# ADC-DMUX.net
KiCad netlist of a schematic drawn in Altium Designer
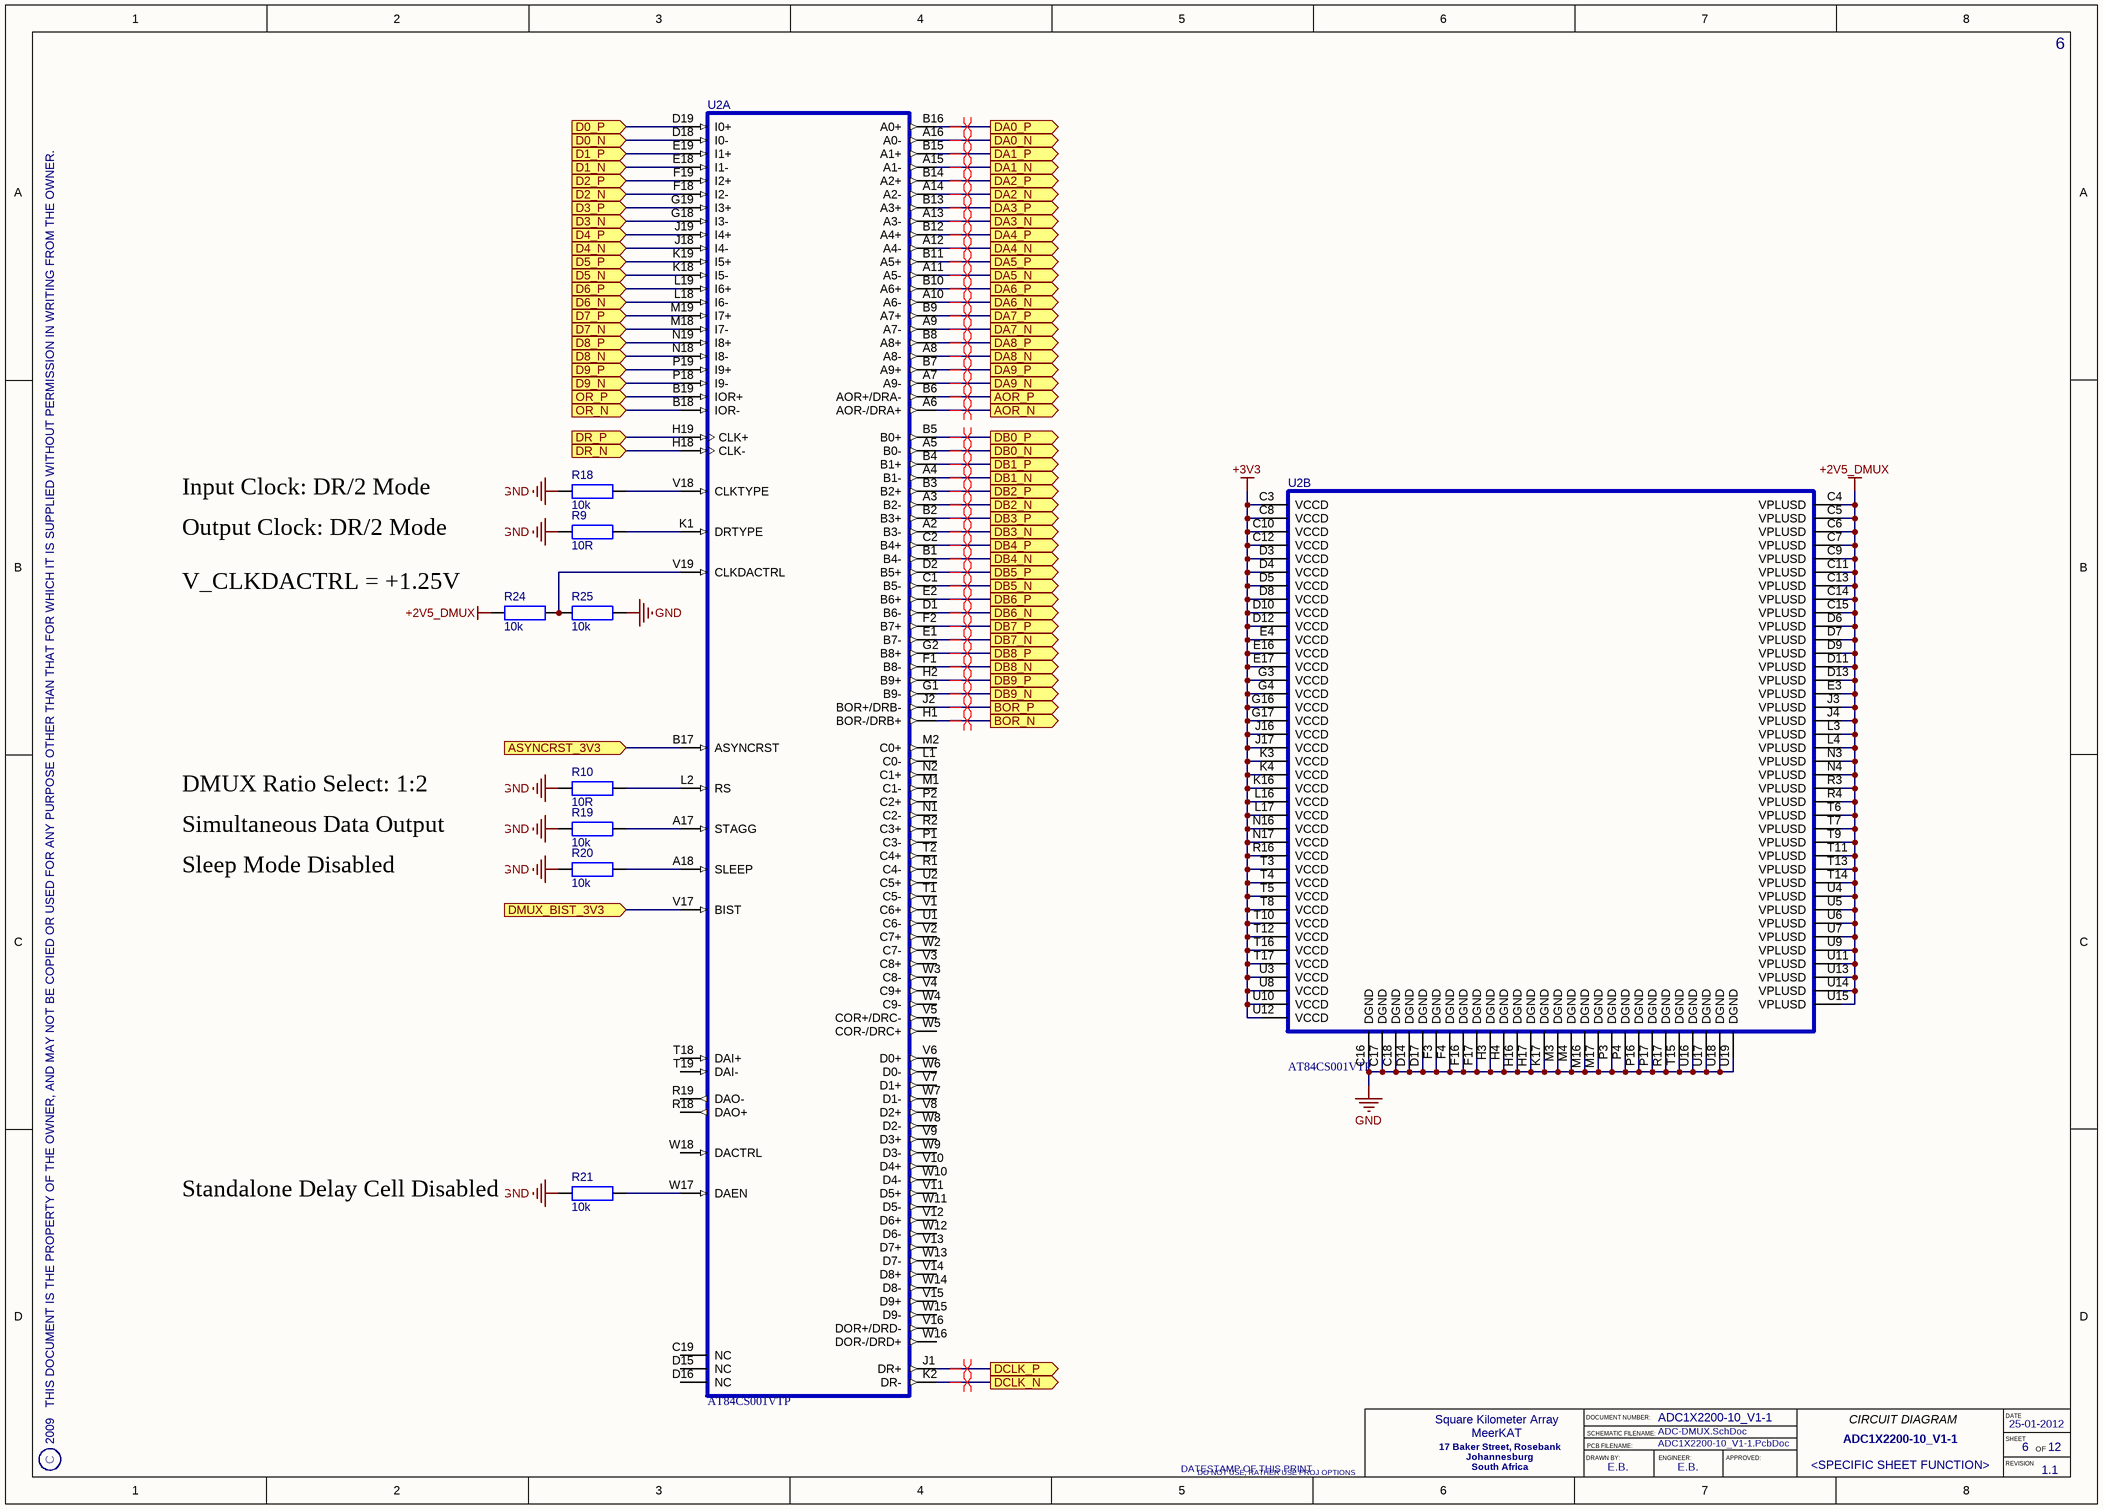
[diagram p0: ADC-DMUX.SchDoc]

(export (version "E")
  (design (tool "Eeschema 10.0.6"))
  (components
    (comp (ref "R9")
      (value "10R")
      (footprint "0603")
      (description "RESISTOR SMD 0603")
      (fields (field (name "CREATED_BY") "*") (field (name "CHECKED_BY") "NN"))
      (libsource (lib "EDA_Passive") (part "RES-0805"))
    )
    (comp (ref "R10")
      (value "10R")
      (footprint "0603")
      (description "RESISTOR SMD 0603")
      (fields (field (name "CREATED_BY") "*") (field (name "CHECKED_BY") "NN"))
      (libsource (lib "EDA_Passive") (part "RES-0805"))
    )
    (comp (ref "R18")
      (value "10k")
      (footprint "0603")
      (description "RESISTOR SMD 0603")
      (fields (field (name "CREATED_BY") "*") (field (name "CHECKED_BY") "NN"))
      (libsource (lib "EDA_Passive") (part "RES-0805"))
    )
    (comp (ref "R19")
      (value "10k")
      (footprint "0603")
      (description "RESISTOR SMD 0603")
      (fields (field (name "CREATED_BY") "*") (field (name "CHECKED_BY") "NN"))
      (libsource (lib "EDA_Passive") (part "RES-0805"))
    )
    (comp (ref "R20")
      (value "10k")
      (footprint "0603")
      (description "RESISTOR SMD 0603")
      (fields (field (name "CREATED_BY") "*") (field (name "CHECKED_BY") "NN"))
      (libsource (lib "EDA_Passive") (part "RES-0805"))
    )
    (comp (ref "R21")
      (value "10k")
      (footprint "0603")
      (description "RESISTOR SMD 0603")
      (fields (field (name "CREATED_BY") "*") (field (name "CHECKED_BY") "NN"))
      (libsource (lib "EDA_Passive") (part "RES-0805"))
    )
    (comp (ref "R24")
      (value "10k")
      (footprint "0603")
      (description "RESISTOR SMD 0603")
      (fields (field (name "CREATED_BY") "*") (field (name "CHECKED_BY") "NN"))
      (libsource (lib "EDA_Passive") (part "RES-0805"))
    )
    (comp (ref "R25")
      (value "10k")
      (footprint "0603")
      (description "RESISTOR SMD 0603")
      (fields (field (name "CREATED_BY") "*") (field (name "CHECKED_BY") "NN"))
      (libsource (lib "EDA_Passive") (part "RES-0805"))
    )
    (comp (ref "U2")
      (value "AT84CS001VTP")
      (footprint "BGA240x19")
      (description "10-bit 2.2Gsps 1:4 DMUX")
      (fields
        (field (name "MANUFACTURER") "e2V")
        (field (name "CREATED_BY") "IN")
        (field (name "CHECKED_BY") "*")
      )
      (libsource (lib "ADC1X2200-10_V1-1") (part "AT84CS001VTP"))
    )
  )
  (nets
    (net (code "1") (name "+2V5_DMUX") (class "Default")
      (node (ref "R24") (pin "1") (pinfunction "1_1") (pintype "passive"))
      (node (ref "U2") (pin "C11") (pinfunction "VPLUSD_C11") (pintype "power_in"))
      (node (ref "U2") (pin "C13") (pinfunction "VPLUSD_C13") (pintype "power_in"))
      (node (ref "U2") (pin "C14") (pinfunction "VPLUSD_C14") (pintype "power_in"))
      (node (ref "U2") (pin "C15") (pinfunction "VPLUSD_C15") (pintype "power_in"))
      (node (ref "U2") (pin "C4") (pinfunction "VPLUSD_C4") (pintype "power_in"))
      (node (ref "U2") (pin "C5") (pinfunction "VPLUSD_C5") (pintype "power_in"))
      (node (ref "U2") (pin "C6") (pinfunction "VPLUSD_C6") (pintype "power_in"))
      (node (ref "U2") (pin "C7") (pinfunction "VPLUSD_C7") (pintype "power_in"))
      (node (ref "U2") (pin "C9") (pinfunction "VPLUSD_C9") (pintype "power_in"))
      (node (ref "U2") (pin "D11") (pinfunction "VPLUSD_D11") (pintype "power_in"))
      (node (ref "U2") (pin "D13") (pinfunction "VPLUSD_D13") (pintype "power_in"))
      (node (ref "U2") (pin "D6") (pinfunction "VPLUSD_D6") (pintype "power_in"))
      (node (ref "U2") (pin "D7") (pinfunction "VPLUSD_D7") (pintype "power_in"))
      (node (ref "U2") (pin "D9") (pinfunction "VPLUSD_D9") (pintype "power_in"))
      (node (ref "U2") (pin "E3") (pinfunction "VPLUSD_E3") (pintype "power_in"))
      (node (ref "U2") (pin "J3") (pinfunction "VPLUSD_J3") (pintype "power_in"))
      (node (ref "U2") (pin "J4") (pinfunction "VPLUSD_J4") (pintype "power_in"))
      (node (ref "U2") (pin "L3") (pinfunction "VPLUSD_L3") (pintype "power_in"))
      (node (ref "U2") (pin "L4") (pinfunction "VPLUSD_L4") (pintype "power_in"))
      (node (ref "U2") (pin "N3") (pinfunction "VPLUSD_N3") (pintype "power_in"))
      (node (ref "U2") (pin "N4") (pinfunction "VPLUSD_N4") (pintype "power_in"))
      (node (ref "U2") (pin "R3") (pinfunction "VPLUSD_R3") (pintype "power_in"))
      (node (ref "U2") (pin "R4") (pinfunction "VPLUSD_R4") (pintype "power_in"))
      (node (ref "U2") (pin "T11") (pinfunction "VPLUSD_T11") (pintype "power_in"))
      (node (ref "U2") (pin "T13") (pinfunction "VPLUSD_T13") (pintype "power_in"))
      (node (ref "U2") (pin "T14") (pinfunction "VPLUSD_T14") (pintype "power_in"))
      (node (ref "U2") (pin "T6") (pinfunction "VPLUSD_T6") (pintype "power_in"))
      (node (ref "U2") (pin "T7") (pinfunction "VPLUSD_T7") (pintype "power_in"))
      (node (ref "U2") (pin "T9") (pinfunction "VPLUSD_T9") (pintype "power_in"))
      (node (ref "U2") (pin "U11") (pinfunction "VPLUSD_U11") (pintype "power_in"))
      (node (ref "U2") (pin "U13") (pinfunction "VPLUSD_U13") (pintype "power_in"))
      (node (ref "U2") (pin "U14") (pinfunction "VPLUSD_U14") (pintype "power_in"))
      (node (ref "U2") (pin "U15") (pinfunction "VPLUSD_U15") (pintype "power_in"))
      (node (ref "U2") (pin "U4") (pinfunction "VPLUSD_U4") (pintype "power_in"))
      (node (ref "U2") (pin "U5") (pinfunction "VPLUSD_U5") (pintype "power_in"))
      (node (ref "U2") (pin "U6") (pinfunction "VPLUSD_U6") (pintype "power_in"))
      (node (ref "U2") (pin "U7") (pinfunction "VPLUSD_U7") (pintype "power_in"))
      (node (ref "U2") (pin "U9") (pinfunction "VPLUSD_U9") (pintype "power_in"))
    )
    (net (code "2") (name "+3V3") (class "Default")
      (node (ref "U2") (pin "C10") (pinfunction "VCCD_C10") (pintype "power_in"))
      (node (ref "U2") (pin "C12") (pinfunction "VCCD_C12") (pintype "power_in"))
      (node (ref "U2") (pin "C3") (pinfunction "VCCD_C3") (pintype "power_in"))
      (node (ref "U2") (pin "C8") (pinfunction "VCCD_C8") (pintype "power_in"))
      (node (ref "U2") (pin "D10") (pinfunction "VCCD_D10") (pintype "power_in"))
      (node (ref "U2") (pin "D12") (pinfunction "VCCD_D12") (pintype "power_in"))
      (node (ref "U2") (pin "D3") (pinfunction "VCCD_D3") (pintype "power_in"))
      (node (ref "U2") (pin "D4") (pinfunction "VCCD_D4") (pintype "power_in"))
      (node (ref "U2") (pin "D5") (pinfunction "VCCD_D5") (pintype "power_in"))
      (node (ref "U2") (pin "D8") (pinfunction "VCCD_D8") (pintype "power_in"))
      (node (ref "U2") (pin "E16") (pinfunction "VCCD_E16") (pintype "power_in"))
      (node (ref "U2") (pin "E17") (pinfunction "VCCD_E17") (pintype "power_in"))
      (node (ref "U2") (pin "E4") (pinfunction "VCCD_E4") (pintype "power_in"))
      (node (ref "U2") (pin "G16") (pinfunction "VCCD_G16") (pintype "power_in"))
      (node (ref "U2") (pin "G17") (pinfunction "VCCD_G17") (pintype "power_in"))
      (node (ref "U2") (pin "G3") (pinfunction "VCCD_G3") (pintype "power_in"))
      (node (ref "U2") (pin "G4") (pinfunction "VCCD_G4") (pintype "power_in"))
      (node (ref "U2") (pin "J16") (pinfunction "VCCD_J16") (pintype "power_in"))
      (node (ref "U2") (pin "J17") (pinfunction "VCCD_J17") (pintype "power_in"))
      (node (ref "U2") (pin "K16") (pinfunction "VCCD_K16") (pintype "power_in"))
      (node (ref "U2") (pin "K3") (pinfunction "VCCD_K3") (pintype "power_in"))
      (node (ref "U2") (pin "K4") (pinfunction "VCCD_K4") (pintype "power_in"))
      (node (ref "U2") (pin "L16") (pinfunction "VCCD_L16") (pintype "power_in"))
      (node (ref "U2") (pin "L17") (pinfunction "VCCD_L17") (pintype "power_in"))
      (node (ref "U2") (pin "N16") (pinfunction "VCCD_N16") (pintype "power_in"))
      (node (ref "U2") (pin "N17") (pinfunction "VCCD_N17") (pintype "power_in"))
      (node (ref "U2") (pin "R16") (pinfunction "VCCD_R16") (pintype "power_in"))
      (node (ref "U2") (pin "T10") (pinfunction "VCCD_T10") (pintype "power_in"))
      (node (ref "U2") (pin "T12") (pinfunction "VCCD_T12") (pintype "power_in"))
      (node (ref "U2") (pin "T16") (pinfunction "VCCD_T16") (pintype "power_in"))
      (node (ref "U2") (pin "T17") (pinfunction "VCCD_T17") (pintype "power_in"))
      (node (ref "U2") (pin "T3") (pinfunction "VCCD_T3") (pintype "power_in"))
      (node (ref "U2") (pin "T4") (pinfunction "VCCD_T4") (pintype "power_in"))
      (node (ref "U2") (pin "T5") (pinfunction "VCCD_T5") (pintype "power_in"))
      (node (ref "U2") (pin "T8") (pinfunction "VCCD_T8") (pintype "power_in"))
      (node (ref "U2") (pin "U10") (pinfunction "VCCD_U10") (pintype "power_in"))
      (node (ref "U2") (pin "U12") (pinfunction "VCCD_U12") (pintype "power_in"))
      (node (ref "U2") (pin "U3") (pinfunction "VCCD_U3") (pintype "power_in"))
      (node (ref "U2") (pin "U8") (pinfunction "VCCD_U8") (pintype "power_in"))
    )
    (net (code "3") (name "/AOR_N") (class "Default")
      (node (ref "U2") (pin "A6") (pinfunction "AOR-/DRA+_A6") (pintype "output"))
    )
    (net (code "4") (name "/AOR_P") (class "Default")
      (node (ref "U2") (pin "B6") (pinfunction "AOR+/DRA-_B6") (pintype "output"))
    )
    (net (code "5") (name "/ASYNCRST_3V3") (class "Default")
      (node (ref "U2") (pin "B17") (pinfunction "ASYNCRST_B17") (pintype "input"))
    )
    (net (code "6") (name "/BOR_N") (class "Default")
      (node (ref "U2") (pin "H1") (pinfunction "BOR-/DRB+_H1") (pintype "output"))
    )
    (net (code "7") (name "/BOR_P") (class "Default")
      (node (ref "U2") (pin "J2") (pinfunction "BOR+/DRB-_J2") (pintype "output"))
    )
    (net (code "8") (name "/D0_N") (class "Default")
      (node (ref "U2") (pin "D18") (pinfunction "I0-_D18") (pintype "input"))
    )
    (net (code "9") (name "/D0_P") (class "Default")
      (node (ref "U2") (pin "D19") (pinfunction "I0+_D19") (pintype "input"))
    )
    (net (code "10") (name "/D1_N") (class "Default")
      (node (ref "U2") (pin "E18") (pinfunction "I1-_E18") (pintype "input"))
    )
    (net (code "11") (name "/D1_P") (class "Default")
      (node (ref "U2") (pin "E19") (pinfunction "I1+_E19") (pintype "input"))
    )
    (net (code "12") (name "/D2_N") (class "Default")
      (node (ref "U2") (pin "F18") (pinfunction "I2-_F18") (pintype "input"))
    )
    (net (code "13") (name "/D2_P") (class "Default")
      (node (ref "U2") (pin "F19") (pinfunction "I2+_F19") (pintype "input"))
    )
    (net (code "14") (name "/D3_N") (class "Default")
      (node (ref "U2") (pin "G18") (pinfunction "I3-_G18") (pintype "input"))
    )
    (net (code "15") (name "/D3_P") (class "Default")
      (node (ref "U2") (pin "G19") (pinfunction "I3+_G19") (pintype "input"))
    )
    (net (code "16") (name "/D4_N") (class "Default")
      (node (ref "U2") (pin "J18") (pinfunction "I4-_J18") (pintype "input"))
    )
    (net (code "17") (name "/D4_P") (class "Default")
      (node (ref "U2") (pin "J19") (pinfunction "I4+_J19") (pintype "input"))
    )
    (net (code "18") (name "/D5_N") (class "Default")
      (node (ref "U2") (pin "K18") (pinfunction "I5-_K18") (pintype "input"))
    )
    (net (code "19") (name "/D5_P") (class "Default")
      (node (ref "U2") (pin "K19") (pinfunction "I5+_K19") (pintype "input"))
    )
    (net (code "20") (name "/D6_N") (class "Default")
      (node (ref "U2") (pin "L18") (pinfunction "I6-_L18") (pintype "input"))
    )
    (net (code "21") (name "/D6_P") (class "Default")
      (node (ref "U2") (pin "L19") (pinfunction "I6+_L19") (pintype "input"))
    )
    (net (code "22") (name "/D7_N") (class "Default")
      (node (ref "U2") (pin "M18") (pinfunction "I7-_M18") (pintype "input"))
    )
    (net (code "23") (name "/D7_P") (class "Default")
      (node (ref "U2") (pin "M19") (pinfunction "I7+_M19") (pintype "input"))
    )
    (net (code "24") (name "/D8_N") (class "Default")
      (node (ref "U2") (pin "N18") (pinfunction "I8-_N18") (pintype "input"))
    )
    (net (code "25") (name "/D8_P") (class "Default")
      (node (ref "U2") (pin "N19") (pinfunction "I8+_N19") (pintype "input"))
    )
    (net (code "26") (name "/D9_N") (class "Default")
      (node (ref "U2") (pin "P18") (pinfunction "I9-_P18") (pintype "input"))
    )
    (net (code "27") (name "/D9_P") (class "Default")
      (node (ref "U2") (pin "P19") (pinfunction "I9+_P19") (pintype "input"))
    )
    (net (code "28") (name "/DA0_N") (class "Default")
      (node (ref "U2") (pin "A16") (pinfunction "A0-_A16") (pintype "output"))
    )
    (net (code "29") (name "/DA0_P") (class "Default")
      (node (ref "U2") (pin "B16") (pinfunction "A0+_B16") (pintype "output"))
    )
    (net (code "30") (name "/DA1_N") (class "Default")
      (node (ref "U2") (pin "A15") (pinfunction "A1-_A15") (pintype "output"))
    )
    (net (code "31") (name "/DA1_P") (class "Default")
      (node (ref "U2") (pin "B15") (pinfunction "A1+_B15") (pintype "output"))
    )
    (net (code "32") (name "/DA2_N") (class "Default")
      (node (ref "U2") (pin "A14") (pinfunction "A2-_A14") (pintype "output"))
    )
    (net (code "33") (name "/DA2_P") (class "Default")
      (node (ref "U2") (pin "B14") (pinfunction "A2+_B14") (pintype "output"))
    )
    (net (code "34") (name "/DA3_N") (class "Default")
      (node (ref "U2") (pin "A13") (pinfunction "A3-_A13") (pintype "output"))
    )
    (net (code "35") (name "/DA3_P") (class "Default")
      (node (ref "U2") (pin "B13") (pinfunction "A3+_B13") (pintype "output"))
    )
    (net (code "36") (name "/DA4_N") (class "Default")
      (node (ref "U2") (pin "A12") (pinfunction "A4-_A12") (pintype "output"))
    )
    (net (code "37") (name "/DA4_P") (class "Default")
      (node (ref "U2") (pin "B12") (pinfunction "A4+_B12") (pintype "output"))
    )
    (net (code "38") (name "/DA5_N") (class "Default")
      (node (ref "U2") (pin "A11") (pinfunction "A5-_A11") (pintype "output"))
    )
    (net (code "39") (name "/DA5_P") (class "Default")
      (node (ref "U2") (pin "B11") (pinfunction "A5+_B11") (pintype "output"))
    )
    (net (code "40") (name "/DA6_N") (class "Default")
      (node (ref "U2") (pin "A10") (pinfunction "A6-_A10") (pintype "output"))
    )
    (net (code "41") (name "/DA6_P") (class "Default")
      (node (ref "U2") (pin "B10") (pinfunction "A6+_B10") (pintype "output"))
    )
    (net (code "42") (name "/DA7_N") (class "Default")
      (node (ref "U2") (pin "A9") (pinfunction "A7-_A9") (pintype "output"))
    )
    (net (code "43") (name "/DA7_P") (class "Default")
      (node (ref "U2") (pin "B9") (pinfunction "A7+_B9") (pintype "output"))
    )
    (net (code "44") (name "/DA8_N") (class "Default")
      (node (ref "U2") (pin "A8") (pinfunction "A8-_A8") (pintype "output"))
    )
    (net (code "45") (name "/DA8_P") (class "Default")
      (node (ref "U2") (pin "B8") (pinfunction "A8+_B8") (pintype "output"))
    )
    (net (code "46") (name "/DA9_N") (class "Default")
      (node (ref "U2") (pin "A7") (pinfunction "A9-_A7") (pintype "output"))
    )
    (net (code "47") (name "/DA9_P") (class "Default")
      (node (ref "U2") (pin "B7") (pinfunction "A9+_B7") (pintype "output"))
    )
    (net (code "48") (name "/DB0_N") (class "Default")
      (node (ref "U2") (pin "A5") (pinfunction "B0-_A5") (pintype "output"))
    )
    (net (code "49") (name "/DB0_P") (class "Default")
      (node (ref "U2") (pin "B5") (pinfunction "B0+_B5") (pintype "output"))
    )
    (net (code "50") (name "/DB1_N") (class "Default")
      (node (ref "U2") (pin "A4") (pinfunction "B1-_A4") (pintype "output"))
    )
    (net (code "51") (name "/DB1_P") (class "Default")
      (node (ref "U2") (pin "B4") (pinfunction "B1+_B4") (pintype "output"))
    )
    (net (code "52") (name "/DB2_N") (class "Default")
      (node (ref "U2") (pin "A3") (pinfunction "B2-_A3") (pintype "output"))
    )
    (net (code "53") (name "/DB2_P") (class "Default")
      (node (ref "U2") (pin "B3") (pinfunction "B2+_B3") (pintype "output"))
    )
    (net (code "54") (name "/DB3_N") (class "Default")
      (node (ref "U2") (pin "A2") (pinfunction "B3-_A2") (pintype "output"))
    )
    (net (code "55") (name "/DB3_P") (class "Default")
      (node (ref "U2") (pin "B2") (pinfunction "B3+_B2") (pintype "output"))
    )
    (net (code "56") (name "/DB4_N") (class "Default")
      (node (ref "U2") (pin "B1") (pinfunction "B4-_B1") (pintype "output"))
    )
    (net (code "57") (name "/DB4_P") (class "Default")
      (node (ref "U2") (pin "C2") (pinfunction "B4+_C2") (pintype "output"))
    )
    (net (code "58") (name "/DB5_N") (class "Default")
      (node (ref "U2") (pin "C1") (pinfunction "B5-_C1") (pintype "output"))
    )
    (net (code "59") (name "/DB5_P") (class "Default")
      (node (ref "U2") (pin "D2") (pinfunction "B5+_D2") (pintype "output"))
    )
    (net (code "60") (name "/DB6_N") (class "Default")
      (node (ref "U2") (pin "D1") (pinfunction "B6-_D1") (pintype "output"))
    )
    (net (code "61") (name "/DB6_P") (class "Default")
      (node (ref "U2") (pin "E2") (pinfunction "B6+_E2") (pintype "output"))
    )
    (net (code "62") (name "/DB7_N") (class "Default")
      (node (ref "U2") (pin "E1") (pinfunction "B7-_E1") (pintype "output"))
    )
    (net (code "63") (name "/DB7_P") (class "Default")
      (node (ref "U2") (pin "F2") (pinfunction "B7+_F2") (pintype "output"))
    )
    (net (code "64") (name "/DB8_N") (class "Default")
      (node (ref "U2") (pin "F1") (pinfunction "B8-_F1") (pintype "output"))
    )
    (net (code "65") (name "/DB8_P") (class "Default")
      (node (ref "U2") (pin "G2") (pinfunction "B8+_G2") (pintype "output"))
    )
    (net (code "66") (name "/DB9_N") (class "Default")
      (node (ref "U2") (pin "G1") (pinfunction "B9-_G1") (pintype "output"))
    )
    (net (code "67") (name "/DB9_P") (class "Default")
      (node (ref "U2") (pin "H2") (pinfunction "B9+_H2") (pintype "output"))
    )
    (net (code "68") (name "/DCLK_N") (class "Default")
      (node (ref "U2") (pin "K2") (pinfunction "DR-_K2") (pintype "output"))
    )
    (net (code "69") (name "/DCLK_P") (class "Default")
      (node (ref "U2") (pin "J1") (pinfunction "DR+_J1") (pintype "output"))
    )
    (net (code "70") (name "/DMUX_BIST_3V3") (class "Default")
      (node (ref "U2") (pin "V17") (pinfunction "BIST_V17") (pintype "input"))
    )
    (net (code "71") (name "/DR_N") (class "Default")
      (node (ref "U2") (pin "H18") (pinfunction "CLK-_H18") (pintype "input"))
    )
    (net (code "72") (name "/DR_P") (class "Default")
      (node (ref "U2") (pin "H19") (pinfunction "CLK+_H19") (pintype "input"))
    )
    (net (code "73") (name "/OR_N") (class "Default")
      (node (ref "U2") (pin "B18") (pinfunction "IOR-_B18") (pintype "input"))
    )
    (net (code "74") (name "/OR_P") (class "Default")
      (node (ref "U2") (pin "B19") (pinfunction "IOR+_B19") (pintype "input"))
    )
    (net (code "75") (name "GND") (class "Default")
      (node (ref "R10") (pin "1") (pinfunction "1_1") (pintype "passive"))
      (node (ref "R18") (pin "1") (pinfunction "1_1") (pintype "passive"))
      (node (ref "R19") (pin "1") (pinfunction "1_1") (pintype "passive"))
      (node (ref "R20") (pin "1") (pinfunction "1_1") (pintype "passive"))
      (node (ref "R21") (pin "1") (pinfunction "1_1") (pintype "passive"))
      (node (ref "R25") (pin "2") (pinfunction "2_2") (pintype "passive"))
      (node (ref "R9") (pin "1") (pinfunction "1_1") (pintype "passive"))
      (node (ref "U2") (pin "C16") (pinfunction "DGND_C16") (pintype "power_in"))
      (node (ref "U2") (pin "C17") (pinfunction "DGND_C17") (pintype "power_in"))
      (node (ref "U2") (pin "C18") (pinfunction "DGND_C18") (pintype "power_in"))
      (node (ref "U2") (pin "D14") (pinfunction "DGND_D14") (pintype "power_in"))
      (node (ref "U2") (pin "D17") (pinfunction "DGND_D17") (pintype "power_in"))
      (node (ref "U2") (pin "F16") (pinfunction "DGND_F16") (pintype "power_in"))
      (node (ref "U2") (pin "F17") (pinfunction "DGND_F17") (pintype "power_in"))
      (node (ref "U2") (pin "F3") (pinfunction "DGND_F3") (pintype "power_in"))
      (node (ref "U2") (pin "F4") (pinfunction "DGND_F4") (pintype "power_in"))
      (node (ref "U2") (pin "H16") (pinfunction "DGND_H16") (pintype "power_in"))
      (node (ref "U2") (pin "H17") (pinfunction "DGND_H17") (pintype "power_in"))
      (node (ref "U2") (pin "H3") (pinfunction "DGND_H3") (pintype "power_in"))
      (node (ref "U2") (pin "H4") (pinfunction "DGND_H4") (pintype "power_in"))
      (node (ref "U2") (pin "K17") (pinfunction "DGND_K17") (pintype "power_in"))
      (node (ref "U2") (pin "M16") (pinfunction "DGND_M16") (pintype "power_in"))
      (node (ref "U2") (pin "M17") (pinfunction "DGND_M17") (pintype "power_in"))
      (node (ref "U2") (pin "M3") (pinfunction "DGND_M3") (pintype "power_in"))
      (node (ref "U2") (pin "M4") (pinfunction "DGND_M4") (pintype "power_in"))
      (node (ref "U2") (pin "P16") (pinfunction "DGND_P16") (pintype "power_in"))
      (node (ref "U2") (pin "P17") (pinfunction "DGND_P17") (pintype "power_in"))
      (node (ref "U2") (pin "P3") (pinfunction "DGND_P3") (pintype "power_in"))
      (node (ref "U2") (pin "P4") (pinfunction "DGND_P4") (pintype "power_in"))
      (node (ref "U2") (pin "R17") (pinfunction "DGND_R17") (pintype "power_in"))
      (node (ref "U2") (pin "T15") (pinfunction "DGND_T15") (pintype "power_in"))
      (node (ref "U2") (pin "U16") (pinfunction "DGND_U16") (pintype "power_in"))
      (node (ref "U2") (pin "U17") (pinfunction "DGND_U17") (pintype "power_in"))
      (node (ref "U2") (pin "U18") (pinfunction "DGND_U18") (pintype "power_in"))
      (node (ref "U2") (pin "U19") (pinfunction "DGND_U19") (pintype "power_in"))
    )
    (net (code "76") (name "Net-(U2A-CLKDACTRL)") (class "Default")
      (node (ref "R24") (pin "2") (pinfunction "2_2") (pintype "passive"))
      (node (ref "R25") (pin "1") (pinfunction "1_1") (pintype "passive"))
      (node (ref "U2") (pin "V19") (pinfunction "CLKDACTRL_V19") (pintype "input"))
    )
    (net (code "77") (name "Net-(U2A-CLKTYPE)") (class "Default")
      (node (ref "R18") (pin "2") (pinfunction "2_2") (pintype "passive"))
      (node (ref "U2") (pin "V18") (pinfunction "CLKTYPE_V18") (pintype "input"))
    )
    (net (code "78") (name "Net-(U2A-DAEN)") (class "Default")
      (node (ref "R21") (pin "2") (pinfunction "2_2") (pintype "passive"))
      (node (ref "U2") (pin "W17") (pinfunction "DAEN_W17") (pintype "input"))
    )
    (net (code "79") (name "Net-(U2A-DRTYPE)") (class "Default")
      (node (ref "R9") (pin "2") (pinfunction "2_2") (pintype "passive"))
      (node (ref "U2") (pin "K1") (pinfunction "DRTYPE_K1") (pintype "input"))
    )
    (net (code "80") (name "Net-(U2A-RS)") (class "Default")
      (node (ref "R10") (pin "2") (pinfunction "2_2") (pintype "passive"))
      (node (ref "U2") (pin "L2") (pinfunction "RS_L2") (pintype "input"))
    )
    (net (code "81") (name "Net-(U2A-SLEEP)") (class "Default")
      (node (ref "R20") (pin "2") (pinfunction "2_2") (pintype "passive"))
      (node (ref "U2") (pin "A18") (pinfunction "SLEEP_A18") (pintype "input"))
    )
    (net (code "82") (name "Net-(U2A-STAGG)") (class "Default")
      (node (ref "R19") (pin "2") (pinfunction "2_2") (pintype "passive"))
      (node (ref "U2") (pin "A17") (pinfunction "STAGG_A17") (pintype "input"))
    )
    (net (code "83") (name "unconnected-(U2A-C0+-PadM2)") (class "Default")
      (node (ref "U2") (pin "M2") (pinfunction "C0+_M2") (pintype "output"))
    )
    (net (code "84") (name "unconnected-(U2A-C0--PadL1)") (class "Default")
      (node (ref "U2") (pin "L1") (pinfunction "C0-_L1") (pintype "output"))
    )
    (net (code "85") (name "unconnected-(U2A-C1+-PadN2)") (class "Default")
      (node (ref "U2") (pin "N2") (pinfunction "C1+_N2") (pintype "output"))
    )
    (net (code "86") (name "unconnected-(U2A-C1--PadM1)") (class "Default")
      (node (ref "U2") (pin "M1") (pinfunction "C1-_M1") (pintype "output"))
    )
    (net (code "87") (name "unconnected-(U2A-C2+-PadP2)") (class "Default")
      (node (ref "U2") (pin "P2") (pinfunction "C2+_P2") (pintype "output"))
    )
    (net (code "88") (name "unconnected-(U2A-C2--PadN1)") (class "Default")
      (node (ref "U2") (pin "N1") (pinfunction "C2-_N1") (pintype "output"))
    )
    (net (code "89") (name "unconnected-(U2A-C3+-PadR2)") (class "Default")
      (node (ref "U2") (pin "R2") (pinfunction "C3+_R2") (pintype "output"))
    )
    (net (code "90") (name "unconnected-(U2A-C3--PadP1)") (class "Default")
      (node (ref "U2") (pin "P1") (pinfunction "C3-_P1") (pintype "output"))
    )
    (net (code "91") (name "unconnected-(U2A-C4+-PadT2)") (class "Default")
      (node (ref "U2") (pin "T2") (pinfunction "C4+_T2") (pintype "output"))
    )
    (net (code "92") (name "unconnected-(U2A-C4--PadR1)") (class "Default")
      (node (ref "U2") (pin "R1") (pinfunction "C4-_R1") (pintype "output"))
    )
    (net (code "93") (name "unconnected-(U2A-C5+-PadU2)") (class "Default")
      (node (ref "U2") (pin "U2") (pinfunction "C5+_U2") (pintype "output"))
    )
    (net (code "94") (name "unconnected-(U2A-C5--PadT1)") (class "Default")
      (node (ref "U2") (pin "T1") (pinfunction "C5-_T1") (pintype "output"))
    )
    (net (code "95") (name "unconnected-(U2A-C6+-PadV1)") (class "Default")
      (node (ref "U2") (pin "V1") (pinfunction "C6+_V1") (pintype "output"))
    )
    (net (code "96") (name "unconnected-(U2A-C6--PadU1)") (class "Default")
      (node (ref "U2") (pin "U1") (pinfunction "C6-_U1") (pintype "output"))
    )
    (net (code "97") (name "unconnected-(U2A-C7+-PadV2)") (class "Default")
      (node (ref "U2") (pin "V2") (pinfunction "C7+_V2") (pintype "output"))
    )
    (net (code "98") (name "unconnected-(U2A-C7--PadW2)") (class "Default")
      (node (ref "U2") (pin "W2") (pinfunction "C7-_W2") (pintype "output"))
    )
    (net (code "99") (name "unconnected-(U2A-C8+-PadV3)") (class "Default")
      (node (ref "U2") (pin "V3") (pinfunction "C8+_V3") (pintype "output"))
    )
    (net (code "100") (name "unconnected-(U2A-C8--PadW3)") (class "Default")
      (node (ref "U2") (pin "W3") (pinfunction "C8-_W3") (pintype "output"))
    )
    (net (code "101") (name "unconnected-(U2A-C9+-PadV4)") (class "Default")
      (node (ref "U2") (pin "V4") (pinfunction "C9+_V4") (pintype "output"))
    )
    (net (code "102") (name "unconnected-(U2A-C9--PadW4)") (class "Default")
      (node (ref "U2") (pin "W4") (pinfunction "C9-_W4") (pintype "output"))
    )
    (net (code "103") (name "unconnected-(U2A-COR+{slash}DRC--PadV5)") (class "Default")
      (node (ref "U2") (pin "V5") (pinfunction "COR+/DRC-_V5") (pintype "output"))
    )
    (net (code "104") (name "unconnected-(U2A-COR-{slash}DRC+-PadW5)") (class "Default")
      (node (ref "U2") (pin "W5") (pinfunction "COR-/DRC+_W5") (pintype "output"))
    )
    (net (code "105") (name "unconnected-(U2A-D0+-PadV6)") (class "Default")
      (node (ref "U2") (pin "V6") (pinfunction "D0+_V6") (pintype "output"))
    )
    (net (code "106") (name "unconnected-(U2A-D0--PadW6)") (class "Default")
      (node (ref "U2") (pin "W6") (pinfunction "D0-_W6") (pintype "output"))
    )
    (net (code "107") (name "unconnected-(U2A-D1+-PadV7)") (class "Default")
      (node (ref "U2") (pin "V7") (pinfunction "D1+_V7") (pintype "output"))
    )
    (net (code "108") (name "unconnected-(U2A-D1--PadW7)") (class "Default")
      (node (ref "U2") (pin "W7") (pinfunction "D1-_W7") (pintype "output"))
    )
    (net (code "109") (name "unconnected-(U2A-D2+-PadV8)") (class "Default")
      (node (ref "U2") (pin "V8") (pinfunction "D2+_V8") (pintype "output"))
    )
    (net (code "110") (name "unconnected-(U2A-D2--PadW8)") (class "Default")
      (node (ref "U2") (pin "W8") (pinfunction "D2-_W8") (pintype "output"))
    )
    (net (code "111") (name "unconnected-(U2A-D3+-PadV9)") (class "Default")
      (node (ref "U2") (pin "V9") (pinfunction "D3+_V9") (pintype "output"))
    )
    (net (code "112") (name "unconnected-(U2A-D3--PadW9)") (class "Default")
      (node (ref "U2") (pin "W9") (pinfunction "D3-_W9") (pintype "output"))
    )
    (net (code "113") (name "unconnected-(U2A-D4+-PadV10)") (class "Default")
      (node (ref "U2") (pin "V10") (pinfunction "D4+_V10") (pintype "output"))
    )
    (net (code "114") (name "unconnected-(U2A-D4--PadW10)") (class "Default")
      (node (ref "U2") (pin "W10") (pinfunction "D4-_W10") (pintype "output"))
    )
    (net (code "115") (name "unconnected-(U2A-D5+-PadV11)") (class "Default")
      (node (ref "U2") (pin "V11") (pinfunction "D5+_V11") (pintype "output"))
    )
    (net (code "116") (name "unconnected-(U2A-D5--PadW11)") (class "Default")
      (node (ref "U2") (pin "W11") (pinfunction "D5-_W11") (pintype "output"))
    )
    (net (code "117") (name "unconnected-(U2A-D6+-PadV12)") (class "Default")
      (node (ref "U2") (pin "V12") (pinfunction "D6+_V12") (pintype "output"))
    )
    (net (code "118") (name "unconnected-(U2A-D6--PadW12)") (class "Default")
      (node (ref "U2") (pin "W12") (pinfunction "D6-_W12") (pintype "output"))
    )
    (net (code "119") (name "unconnected-(U2A-D7+-PadV13)") (class "Default")
      (node (ref "U2") (pin "V13") (pinfunction "D7+_V13") (pintype "output"))
    )
    (net (code "120") (name "unconnected-(U2A-D7--PadW13)") (class "Default")
      (node (ref "U2") (pin "W13") (pinfunction "D7-_W13") (pintype "output"))
    )
    (net (code "121") (name "unconnected-(U2A-D8+-PadV14)") (class "Default")
      (node (ref "U2") (pin "V14") (pinfunction "D8+_V14") (pintype "output"))
    )
    (net (code "122") (name "unconnected-(U2A-D8--PadW14)") (class "Default")
      (node (ref "U2") (pin "W14") (pinfunction "D8-_W14") (pintype "output"))
    )
    (net (code "123") (name "unconnected-(U2A-D9+-PadV15)") (class "Default")
      (node (ref "U2") (pin "V15") (pinfunction "D9+_V15") (pintype "output"))
    )
    (net (code "124") (name "unconnected-(U2A-D9--PadW15)") (class "Default")
      (node (ref "U2") (pin "W15") (pinfunction "D9-_W15") (pintype "output"))
    )
    (net (code "125") (name "unconnected-(U2A-DACTRL-PadW18)") (class "Default")
      (node (ref "U2") (pin "W18") (pinfunction "DACTRL_W18") (pintype "input"))
    )
    (net (code "126") (name "unconnected-(U2A-DAI+-PadT18)") (class "Default")
      (node (ref "U2") (pin "T18") (pinfunction "DAI+_T18") (pintype "input"))
    )
    (net (code "127") (name "unconnected-(U2A-DAI--PadT19)") (class "Default")
      (node (ref "U2") (pin "T19") (pinfunction "DAI-_T19") (pintype "input"))
    )
    (net (code "128") (name "unconnected-(U2A-DAO+-PadR18)") (class "Default")
      (node (ref "U2") (pin "R18") (pinfunction "DAO+_R18") (pintype "output"))
    )
    (net (code "129") (name "unconnected-(U2A-DAO--PadR19)") (class "Default")
      (node (ref "U2") (pin "R19") (pinfunction "DAO-_R19") (pintype "output"))
    )
    (net (code "130") (name "unconnected-(U2A-DOR+{slash}DRD--PadV16)") (class "Default")
      (node (ref "U2") (pin "V16") (pinfunction "DOR+/DRD-_V16") (pintype "output"))
    )
    (net (code "131") (name "unconnected-(U2A-DOR-{slash}DRD+-PadW16)") (class "Default")
      (node (ref "U2") (pin "W16") (pinfunction "DOR-/DRD+_W16") (pintype "output"))
    )
    (net (code "132") (name "unconnected-(U2A-NC-PadC19)") (class "Default")
      (node (ref "U2") (pin "C19") (pinfunction "NC_C19") (pintype "passive"))
    )
    (net (code "133") (name "unconnected-(U2A-NC-PadD15)") (class "Default")
      (node (ref "U2") (pin "D15") (pinfunction "NC_D15") (pintype "passive"))
    )
    (net (code "134") (name "unconnected-(U2A-NC-PadD16)") (class "Default")
      (node (ref "U2") (pin "D16") (pinfunction "NC_D16") (pintype "passive"))
    )
  )
)
